# Power.net
KiCad netlist of a schematic drawn in Altium Designer
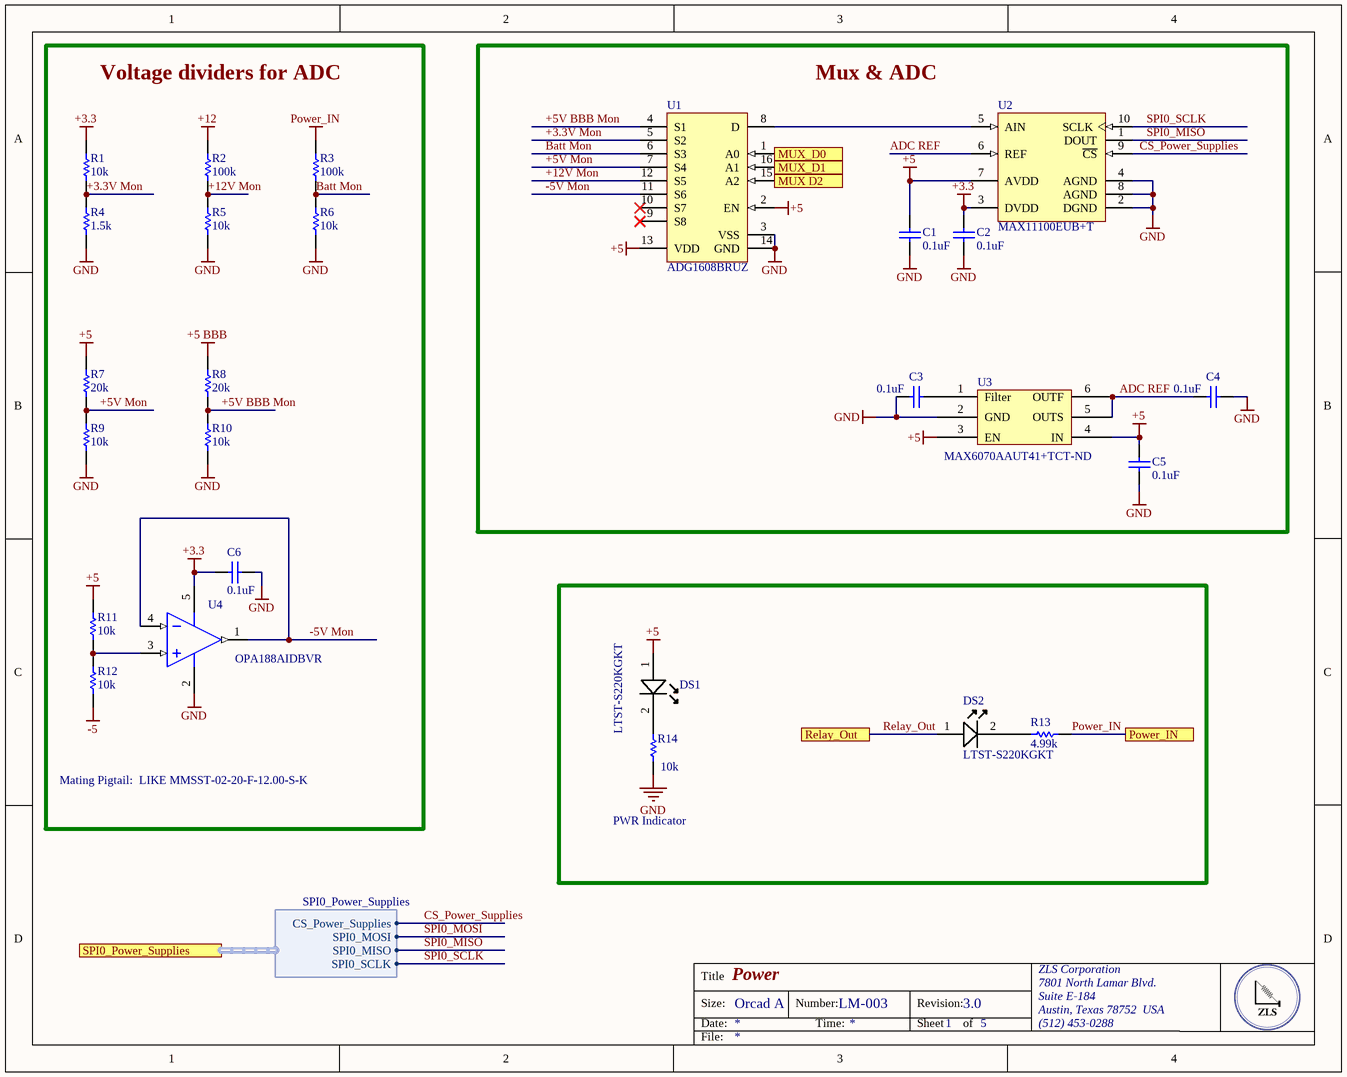
[diagram p0: Power.SchDoc]

(export (version "E")
  (design (tool "Eeschema 10.0.6"))
  (components
    (comp (ref "C1")
      (value "0.1uF")
      (footprint "CAPC0402(1005)60_L")
      (description "CAP CER 0.1UF 10V X7R 0402")
      (fields
        (field (name "MANUFACTURER") "Murata Electronics North America")
        (field (name "MANUFACTURER PART NUMBER") "GRM155R71A104KA01D")
      )
      (libsource (lib "Altium Content Vault") (part "CMP-1034-00252-1"))
    )
    (comp (ref "C2")
      (value "0.1uF")
      (footprint "CAPC0402(1005)60_L")
      (description "CAP CER 0.1UF 10V X7R 0402")
      (fields
        (field (name "MANUFACTURER") "Murata Electronics North America")
        (field (name "MANUFACTURER PART NUMBER") "GRM155R71A104KA01D")
      )
      (libsource (lib "Altium Content Vault") (part "CMP-1034-00252-1"))
    )
    (comp (ref "C3")
      (value "0.1uF")
      (footprint "CAPC0402(1005)60_L")
      (description "CAP CER 0.1UF 10V X7R 0402")
      (fields
        (field (name "MANUFACTURER") "Murata Electronics North America")
        (field (name "MANUFACTURER PART NUMBER") "GRM155R71A104KA01D")
      )
      (libsource (lib "Altium Content Vault") (part "CMP-1034-00252-1"))
    )
    (comp (ref "C4")
      (value "0.1uF")
      (footprint "CAPC0402(1005)60_L")
      (description "CAP CER 0.1UF 10V X7R 0402")
      (fields
        (field (name "MANUFACTURER") "Murata Electronics North America")
        (field (name "MANUFACTURER PART NUMBER") "GRM155R71A104KA01D")
      )
      (libsource (lib "Altium Content Vault") (part "CMP-1034-00252-1"))
    )
    (comp (ref "C5")
      (value "0.1uF")
      (footprint "CAPC0402(1005)60_L")
      (description "CAP CER 0.1UF 10V X7R 0402")
      (fields
        (field (name "MANUFACTURER") "Murata Electronics North America")
        (field (name "MANUFACTURER PART NUMBER") "GRM155R71A104KA01D")
      )
      (libsource (lib "Altium Content Vault") (part "CMP-1034-00252-1"))
    )
    (comp (ref "C6")
      (value "0.1uF")
      (footprint "CAPC0402(1005)60_L")
      (description "CAP CER 0.1UF 10V X7R 0402")
      (fields
        (field (name "MANUFACTURER") "Murata Electronics North America")
        (field (name "MANUFACTURER PART NUMBER") "GRM155R71A104KA01D")
      )
      (libsource (lib "Altium Content Vault") (part "CMP-1034-00252-1"))
    )
    (comp (ref "DS1")
      (value "Lite-On LTST-S220KGKT Green LED, 571 nm 2012 (0805) Side View, Rectangle Lens SMD package")
      (footprint "0805C_L")
      (fields
        (field (name "MANUFACTURER") "Vishay / Lite-On")
        (field (name "MANUFACTURER PART NUMBER") "LTST-S220KGKT")
      )
      (libsource (lib "*") (part "LED A/K"))
    )
    (comp (ref "DS2")
      (value "Lite-On LTST-S220KGKT Green LED, 571 nm 2012 (0805) Side View, Rectangle Lens SMD package")
      (footprint "0805C_L")
      (fields
        (field (name "MANUFACTURER") "Vishay / Lite-On")
        (field (name "MANUFACTURER PART NUMBER") "LTST-S220KGKT")
      )
      (libsource (lib "*") (part "LED A/K"))
    )
    (comp (ref "R1")
      (value "10k")
      (footprint "RESC0402(1005)_M")
      (libsource (lib "Altium Content Vault") (part "CMP-1011-00651-1"))
    )
    (comp (ref "R2")
      (value "100k")
      (footprint "RESC0402(1005)_M")
      (libsource (lib "Altium Content Vault") (part "CMP-1011-00651-1"))
    )
    (comp (ref "R3")
      (value "100k")
      (footprint "RESC0402(1005)_M")
      (libsource (lib "Altium Content Vault") (part "CMP-1011-00651-1"))
    )
    (comp (ref "R4")
      (value "1.5k")
      (footprint "RESC0402(1005)_M")
      (libsource (lib "Altium Content Vault") (part "CMP-1011-00651-1"))
    )
    (comp (ref "R5")
      (value "10k")
      (footprint "RESC0402(1005)_M")
      (libsource (lib "Altium Content Vault") (part "CMP-1011-00651-1"))
    )
    (comp (ref "R6")
      (value "10k")
      (footprint "RESC0402(1005)_M")
      (libsource (lib "Altium Content Vault") (part "CMP-1011-00651-1"))
    )
    (comp (ref "R7")
      (value "20k")
      (footprint "RESC0402(1005)_M")
      (libsource (lib "Altium Content Vault") (part "CMP-1011-00651-1"))
    )
    (comp (ref "R8")
      (value "20k")
      (footprint "RESC0402(1005)_M")
      (libsource (lib "Altium Content Vault") (part "CMP-1011-00651-1"))
    )
    (comp (ref "R9")
      (value "10k")
      (footprint "RESC0402(1005)_M")
      (libsource (lib "Altium Content Vault") (part "CMP-1011-00651-1"))
    )
    (comp (ref "R10")
      (value "10k")
      (footprint "RESC0402(1005)_M")
      (libsource (lib "Altium Content Vault") (part "CMP-1011-00651-1"))
    )
    (comp (ref "R11")
      (value "10k")
      (footprint "RESC0402(1005)_M")
      (libsource (lib "Altium Content Vault") (part "CMP-1011-00651-1"))
    )
    (comp (ref "R12")
      (value "10k")
      (footprint "RESC0402(1005)_M")
      (libsource (lib "Altium Content Vault") (part "CMP-1011-00651-1"))
    )
    (comp (ref "R13")
      (value "4.99k")
      (footprint "RESC0402(1005)_M")
      (libsource (lib "Altium Content Vault") (part "CMP-1011-00651-1"))
    )
    (comp (ref "R14")
      (value "10k")
      (footprint "RESC0402(1005)_M")
      (libsource (lib "Altium Content Vault") (part "CMP-1011-00651-1"))
    )
    (comp (ref "U1")
      (value "ADG1608BRUZ")
      (footprint "ADI-RU-16_M")
      (description "4.5 Ohm Ron, 8-Channel +/-5 V,+12 V, +5 V and +3.3 V Multiplexer, 16-pin SOP (RU-16), Tube")
      (fields (field (name "MANUFACTURER") "Analog Devices"))
      (libsource (lib "Altium Content Vault") (part "ADI-ADG1608-RU-16"))
    )
    (comp (ref "U2")
      (value "MAX11100EUB+T")
      (footprint "U10+2_L")
      (description "16-Bit, +5V, 200ksps ADC with 10uA Shutdown, 10-Pin uMAX, -40°C to +85°C, Pb-Free, Tape and Reel")
      (libsource (lib "Altium Content Vault") (part "CON-ADC-MAX11100-IL10"))
    )
    (comp (ref "U3")
      (value "MAX6070AAUT41+T")
      (footprint "SOT95P280X445-6N")
      (description "IC VREF SERIES 4.096V SOT23")
      (fields
        (field (name "SUPPLIER PART NUMBER 1") "MAX6070AAUT41+TCT-ND")
        (field (name "MANUFACTURER") "Maxim Integrated")
        (field (name "TOLERANCE") "±0.04%")
      )
      (libsource (lib "ZLS_Schematic_lib") (part "MAX6070AAUT41+T"))
    )
    (comp (ref "U4")
      (value "OPA188AIDBVR")
      (footprint "DBV0005A_M")
      (fields (field (name "MANUFACTURER") "Texas Instruments"))
      (libsource (lib "Altium Content Vault") (part "CMP-0809-00005-2"))
    )
  )
  (nets
    (net (code "2") (name "+3.3") (class "Default")
      (node (ref "C2") (pin "1") (pinfunction "1_1") (pintype "passive"))
      (node (ref "C6") (pin "1") (pinfunction "1_1") (pintype "passive"))
      (node (ref "R1") (pin "2") (pinfunction "2_2") (pintype "passive"))
      (node (ref "U2") (pin "3") (pinfunction "DVDD_3") (pintype "power_in"))
      (node (ref "U4") (pin "5") (pinfunction "V+_5") (pintype "power_in"))
    )
    (net (code "3") (name "+5") (class "Default")
      (node (ref "C1") (pin "1") (pinfunction "1_1") (pintype "passive"))
      (node (ref "C5") (pin "1") (pinfunction "1_1") (pintype "passive"))
      (node (ref "DS1") (pin "1") (pinfunction "A_1") (pintype "passive"))
      (node (ref "R11") (pin "2") (pinfunction "2_2") (pintype "passive"))
      (node (ref "R7") (pin "2") (pinfunction "2_2") (pintype "passive"))
      (node (ref "U1") (pin "13") (pinfunction "VDD_13") (pintype "power_in"))
      (node (ref "U1") (pin "2") (pinfunction "EN_2") (pintype "input"))
      (node (ref "U2") (pin "7") (pinfunction "AVDD_7") (pintype "power_in"))
      (node (ref "U3") (pin "3") (pinfunction "EN_3") (pintype "passive"))
      (node (ref "U3") (pin "4") (pinfunction "IN_4") (pintype "passive"))
    )
    (net (code "4") (name "+5 BBB") (class "Default")
      (node (ref "R8") (pin "2") (pinfunction "2_2") (pintype "passive"))
    )
    (net (code "5") (name "+12") (class "Default")
      (node (ref "R2") (pin "2") (pinfunction "2_2") (pintype "passive"))
    )
    (net (code "6") (name "-5") (class "Default")
      (node (ref "R12") (pin "1") (pinfunction "1_1") (pintype "passive"))
    )
    (net (code "7") (name "/+3.3V Mon") (class "Default")
      (node (ref "R1") (pin "1") (pinfunction "1_1") (pintype "passive"))
      (node (ref "R4") (pin "2") (pinfunction "2_2") (pintype "passive"))
      (node (ref "U1") (pin "5") (pinfunction "S2_5") (pintype "passive"))
    )
    (net (code "8") (name "/+5V BBB Mon") (class "Default")
      (node (ref "R10") (pin "2") (pinfunction "2_2") (pintype "passive"))
      (node (ref "R8") (pin "1") (pinfunction "1_1") (pintype "passive"))
      (node (ref "U1") (pin "4") (pinfunction "S1_4") (pintype "passive"))
    )
    (net (code "9") (name "/+5V Mon") (class "Default")
      (node (ref "R7") (pin "1") (pinfunction "1_1") (pintype "passive"))
      (node (ref "R9") (pin "2") (pinfunction "2_2") (pintype "passive"))
      (node (ref "U1") (pin "7") (pinfunction "S4_7") (pintype "passive"))
    )
    (net (code "10") (name "/+12V Mon") (class "Default")
      (node (ref "R2") (pin "1") (pinfunction "1_1") (pintype "passive"))
      (node (ref "R5") (pin "2") (pinfunction "2_2") (pintype "passive"))
      (node (ref "U1") (pin "12") (pinfunction "S5_12") (pintype "passive"))
    )
    (net (code "11") (name "/-5V Mon") (class "Default")
      (node (ref "U1") (pin "11") (pinfunction "S6_11") (pintype "passive"))
      (node (ref "U4") (pin "1") (pinfunction "OUT_1") (pintype "output"))
      (node (ref "U4") (pin "4") (pinfunction "IN-_4") (pintype "input"))
    )
    (net (code "12") (name "/ADC REF") (class "Default")
      (node (ref "C4") (pin "2") (pinfunction "2_2") (pintype "passive"))
      (node (ref "U2") (pin "6") (pinfunction "REF_6") (pintype "input"))
      (node (ref "U3") (pin "5") (pinfunction "OUTS_5") (pintype "passive"))
      (node (ref "U3") (pin "6") (pinfunction "OUTF_6") (pintype "passive"))
    )
    (net (code "13") (name "/Batt Mon") (class "Default")
      (node (ref "R3") (pin "1") (pinfunction "1_1") (pintype "passive"))
      (node (ref "R6") (pin "2") (pinfunction "2_2") (pintype "passive"))
      (node (ref "U1") (pin "6") (pinfunction "S3_6") (pintype "passive"))
    )
    (net (code "14") (name "/CS_Power_Supplies") (class "Default")
      (node (ref "U2") (pin "9") (pinfunction "~{CS}_9") (pintype "input"))
    )
    (net (code "15") (name "/MUX D2") (class "Default")
      (node (ref "U1") (pin "15") (pinfunction "A2_15") (pintype "input"))
    )
    (net (code "16") (name "/MUX_D0") (class "Default")
      (node (ref "U1") (pin "1") (pinfunction "A0_1") (pintype "input"))
    )
    (net (code "17") (name "/MUX_D1") (class "Default")
      (node (ref "U1") (pin "16") (pinfunction "A1_16") (pintype "input"))
    )
    (net (code "18") (name "/Relay_Out") (class "Default")
      (node (ref "DS2") (pin "1") (pinfunction "A_1") (pintype "passive"))
    )
    (net (code "19") (name "/SPI0_MISO") (class "Default")
      (node (ref "U2") (pin "1") (pinfunction "DOUT_1") (pintype "tri_state"))
    )
    (net (code "21") (name "/SPI0_SCLK") (class "Default")
      (node (ref "U2") (pin "10") (pinfunction "SCLK_10") (pintype "input"))
    )
    (net (code "23") (name "GND") (class "Default")
      (node (ref "C1") (pin "2") (pinfunction "2_2") (pintype "passive"))
      (node (ref "C2") (pin "2") (pinfunction "2_2") (pintype "passive"))
      (node (ref "C3") (pin "2") (pinfunction "2_2") (pintype "passive"))
      (node (ref "C4") (pin "1") (pinfunction "1_1") (pintype "passive"))
      (node (ref "C5") (pin "2") (pinfunction "2_2") (pintype "passive"))
      (node (ref "C6") (pin "2") (pinfunction "2_2") (pintype "passive"))
      (node (ref "R10") (pin "1") (pinfunction "1_1") (pintype "passive"))
      (node (ref "R14") (pin "2") (pinfunction "2_2") (pintype "passive"))
      (node (ref "R4") (pin "1") (pinfunction "1_1") (pintype "passive"))
      (node (ref "R5") (pin "1") (pinfunction "1_1") (pintype "passive"))
      (node (ref "R6") (pin "1") (pinfunction "1_1") (pintype "passive"))
      (node (ref "R9") (pin "1") (pinfunction "1_1") (pintype "passive"))
      (node (ref "U1") (pin "14") (pinfunction "GND_14") (pintype "power_in"))
      (node (ref "U1") (pin "3") (pinfunction "VSS_3") (pintype "power_in"))
      (node (ref "U2") (pin "2") (pinfunction "DGND_2") (pintype "power_in"))
      (node (ref "U2") (pin "4") (pinfunction "AGND_4") (pintype "power_in"))
      (node (ref "U2") (pin "8") (pinfunction "AGND_8") (pintype "power_in"))
      (node (ref "U3") (pin "2") (pinfunction "GND_2") (pintype "passive"))
      (node (ref "U4") (pin "2") (pinfunction "V-_2") (pintype "power_in"))
    )
    (net (code "24") (name "Net-(DS1-K)") (class "Default")
      (node (ref "DS1") (pin "2") (pinfunction "K_2") (pintype "passive"))
      (node (ref "R14") (pin "1") (pinfunction "1_1") (pintype "passive"))
    )
    (net (code "25") (name "Net-(DS2-K)") (class "Default")
      (node (ref "DS2") (pin "2") (pinfunction "K_2") (pintype "passive"))
      (node (ref "R13") (pin "1") (pinfunction "1_1") (pintype "passive"))
    )
    (net (code "26") (name "Net-(U1-D)") (class "Default")
      (node (ref "U1") (pin "8") (pinfunction "D_8") (pintype "passive"))
      (node (ref "U2") (pin "5") (pinfunction "AIN_5") (pintype "input"))
    )
    (net (code "27") (name "Net-(U3-Filter)") (class "Default")
      (node (ref "C3") (pin "1") (pinfunction "1_1") (pintype "passive"))
      (node (ref "U3") (pin "1") (pinfunction "Filter_1") (pintype "passive"))
    )
    (net (code "28") (name "Net-(U4-IN+)") (class "Default")
      (node (ref "R11") (pin "1") (pinfunction "1_1") (pintype "passive"))
      (node (ref "R12") (pin "2") (pinfunction "2_2") (pintype "passive"))
      (node (ref "U4") (pin "3") (pinfunction "IN+_3") (pintype "input"))
    )
    (net (code "29") (name "Power_IN") (class "Default")
      (node (ref "R13") (pin "2") (pinfunction "2_2") (pintype "passive"))
      (node (ref "R3") (pin "2") (pinfunction "2_2") (pintype "passive"))
    )
    (net (code "30") (name "unconnected-(U1-S7-Pad10)") (class "Default")
      (node (ref "U1") (pin "10") (pinfunction "S7_10") (pintype "passive+no_connect"))
    )
    (net (code "31") (name "unconnected-(U1-S8-Pad9)") (class "Default")
      (node (ref "U1") (pin "9") (pinfunction "S8_9") (pintype "passive+no_connect"))
    )
  )
)
